# H-bro_gear.net
KiCad netlist of a schematic drawn in EAGLE
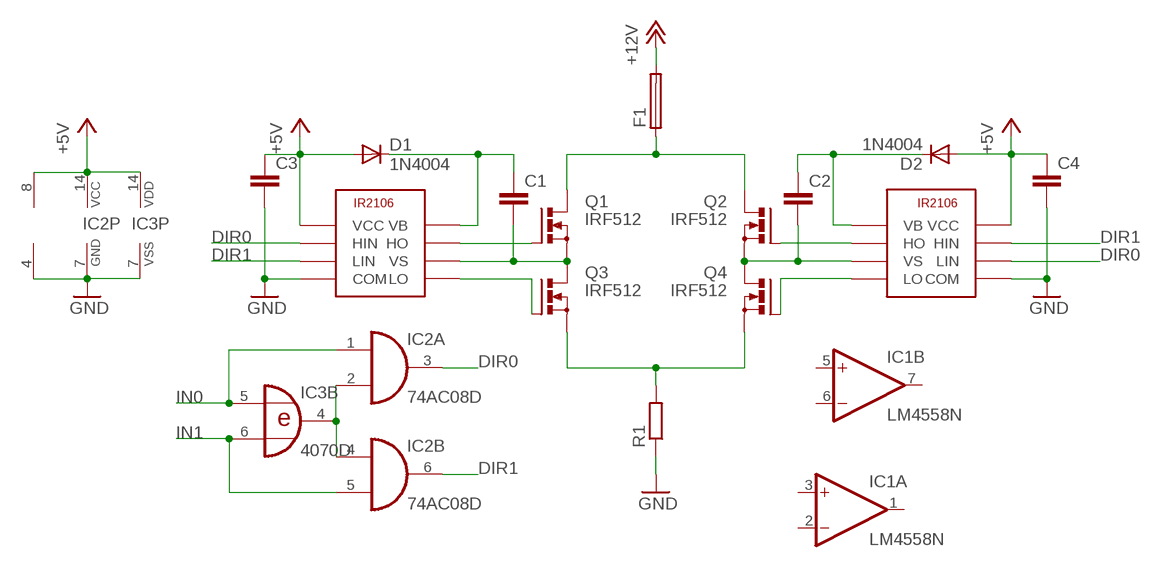
[diagram p0: schematic, sheet 1]

(export (version "E")
  (design (tool "Eeschema 10.0.6"))
  (components
    (comp (ref "C1")
      (value "C-EU025-025X050")
      (footprint "eagle-import:C025-025X050")
      (libsource (lib "eagle-import") (part "C-EU025-025X050"))
    )
    (comp (ref "C2")
      (value "C-EU025-025X050")
      (footprint "eagle-import:C025-025X050")
      (libsource (lib "eagle-import") (part "C-EU025-025X050"))
    )
    (comp (ref "C3")
      (value "C-EU025-025X050")
      (footprint "eagle-import:C025-025X050")
      (libsource (lib "eagle-import") (part "C-EU025-025X050"))
    )
    (comp (ref "C4")
      (value "C-EU025-025X050")
      (footprint "eagle-import:C025-025X050")
      (libsource (lib "eagle-import") (part "C-EU025-025X050"))
    )
    (comp (ref "D1")
      (value "1N4004")
      (footprint "eagle-import:DO41-10")
      (libsource (lib "eagle-import") (part "1N4004"))
    )
    (comp (ref "D2")
      (value "1N4004")
      (footprint "eagle-import:DO41-10")
      (libsource (lib "eagle-import") (part "1N4004"))
    )
    (comp (ref "F1")
      (value "PICOFUSE")
      (footprint "eagle-import:PICOFUSE")
      (libsource (lib "eagle-import") (part "PICOFUSE"))
    )
    (comp (ref "IC1")
      (value "LM4558N")
      (footprint "eagle-import:DIL08")
      (libsource (lib "eagle-import") (part "4558NLM"))
    )
    (comp (ref "IC2")
      (value "74AC08D")
      (footprint "eagle-import:SO14")
      (libsource (lib "eagle-import") (part "7408DAC"))
    )
    (comp (ref "IC3")
      (value "4070D")
      (footprint "eagle-import:SO14")
      (libsource (lib "eagle-import") (part "4070D"))
    )
    (comp (ref "Q1")
      (value "IRF512")
      (footprint "eagle-import:TO220BV")
      (libsource (lib "eagle-import") (part "IRF512"))
    )
    (comp (ref "Q2")
      (value "IRF512")
      (footprint "eagle-import:TO220BV")
      (libsource (lib "eagle-import") (part "IRF512"))
    )
    (comp (ref "Q3")
      (value "IRF512")
      (footprint "eagle-import:TO220BV")
      (libsource (lib "eagle-import") (part "IRF512"))
    )
    (comp (ref "Q4")
      (value "IRF512")
      (footprint "eagle-import:TO220BV")
      (libsource (lib "eagle-import") (part "IRF512"))
    )
    (comp (ref "R1")
      (value "R-EU_0309/12")
      (footprint "eagle-import:0309_12")
      (libsource (lib "eagle-import") (part "R-EU_0309/12"))
    )
    (comp (ref "U$1")
      (value "IR2106")
      (footprint "eagle-import:IR2106")
      (libsource (lib "eagle-import") (part "IR2106"))
    )
    (comp (ref "U$2")
      (value "IR2106")
      (footprint "eagle-import:IR2106")
      (libsource (lib "eagle-import") (part "IR2106"))
    )
  )
  (nets
    (net (code "1") (name "+5V") (class "Default")
      (node (ref "C3") (pin "1") (pinfunction "1_1") (pintype "passive"))
      (node (ref "C4") (pin "1") (pinfunction "1_1") (pintype "passive"))
      (node (ref "D1") (pin "A") (pinfunction "A_A") (pintype "passive"))
      (node (ref "D2") (pin "A") (pinfunction "A_A") (pintype "passive"))
      (node (ref "IC1") (pin "8") (pinfunction "V+_8") (pintype "power_in"))
      (node (ref "IC2") (pin "14") (pinfunction "VCC_14") (pintype "power_in"))
      (node (ref "IC3") (pin "14") (pinfunction "VDD_14") (pintype "power_in"))
      (node (ref "U$1") (pin "VCC") (pinfunction "VCC_VCC") (pintype "bidirectional"))
      (node (ref "U$2") (pin "VCC") (pinfunction "VCC_VCC") (pintype "bidirectional"))
    )
    (net (code "2") (name "+12V") (class "Default")
      (node (ref "F1") (pin "2") (pinfunction "2_2") (pintype "passive"))
    )
    (net (code "3") (name "/DIR0") (class "Default")
      (node (ref "IC2") (pin "3") (pinfunction "O_3") (pintype "output"))
      (node (ref "U$1") (pin "HIN") (pinfunction "HIN_HIN") (pintype "bidirectional"))
      (node (ref "U$2") (pin "LIN") (pinfunction "LIN_LIN") (pintype "bidirectional"))
    )
    (net (code "4") (name "/DIR1") (class "Default")
      (node (ref "IC2") (pin "6") (pinfunction "O_6") (pintype "output"))
      (node (ref "U$1") (pin "LIN") (pinfunction "LIN_LIN") (pintype "bidirectional"))
      (node (ref "U$2") (pin "HIN") (pinfunction "HIN_HIN") (pintype "bidirectional"))
    )
    (net (code "5") (name "/IN0") (class "Default")
      (node (ref "IC2") (pin "1") (pinfunction "I0_1") (pintype "input"))
      (node (ref "IC3") (pin "5") (pinfunction "I0_5") (pintype "input"))
    )
    (net (code "6") (name "/IN1") (class "Default")
      (node (ref "IC2") (pin "5") (pinfunction "I1_5") (pintype "input"))
      (node (ref "IC3") (pin "6") (pinfunction "I1_6") (pintype "input"))
    )
    (net (code "7") (name "GND") (class "Default")
      (node (ref "C3") (pin "2") (pinfunction "2_2") (pintype "passive"))
      (node (ref "C4") (pin "2") (pinfunction "2_2") (pintype "passive"))
      (node (ref "IC1") (pin "4") (pinfunction "V-_4") (pintype "power_in"))
      (node (ref "IC2") (pin "7") (pinfunction "GND_7") (pintype "power_in"))
      (node (ref "IC3") (pin "7") (pinfunction "VSS_7") (pintype "power_in"))
      (node (ref "R1") (pin "1") (pinfunction "1_1") (pintype "passive"))
      (node (ref "U$1") (pin "COM") (pinfunction "COM_COM") (pintype "bidirectional"))
      (node (ref "U$2") (pin "COM") (pinfunction "COM_COM") (pintype "bidirectional"))
    )
    (net (code "8") (name "Net-(C1-Pad1)") (class "Default")
      (node (ref "C1") (pin "1") (pinfunction "1_1") (pintype "passive"))
      (node (ref "D1") (pin "C") (pinfunction "C_C") (pintype "passive"))
      (node (ref "U$1") (pin "VB") (pinfunction "VB_VB") (pintype "bidirectional"))
    )
    (net (code "9") (name "Net-(C1-Pad2)") (class "Default")
      (node (ref "C1") (pin "2") (pinfunction "2_2") (pintype "passive"))
      (node (ref "Q1") (pin "S") (pinfunction "S_S") (pintype "passive"))
      (node (ref "Q3") (pin "D") (pinfunction "D_D") (pintype "passive"))
      (node (ref "U$1") (pin "VS") (pinfunction "VS_VS") (pintype "bidirectional"))
    )
    (net (code "10") (name "Net-(C2-Pad1)") (class "Default")
      (node (ref "C2") (pin "1") (pinfunction "1_1") (pintype "passive"))
      (node (ref "D2") (pin "C") (pinfunction "C_C") (pintype "passive"))
      (node (ref "U$2") (pin "VB") (pinfunction "VB_VB") (pintype "bidirectional"))
    )
    (net (code "11") (name "Net-(C2-Pad2)") (class "Default")
      (node (ref "C2") (pin "2") (pinfunction "2_2") (pintype "passive"))
      (node (ref "Q2") (pin "S") (pinfunction "S_S") (pintype "passive"))
      (node (ref "Q4") (pin "D") (pinfunction "D_D") (pintype "passive"))
      (node (ref "U$2") (pin "VS") (pinfunction "VS_VS") (pintype "bidirectional"))
    )
    (net (code "12") (name "Net-(F1-Pad1)") (class "Default")
      (node (ref "F1") (pin "1") (pinfunction "1_1") (pintype "passive"))
      (node (ref "Q1") (pin "D") (pinfunction "D_D") (pintype "passive"))
      (node (ref "Q2") (pin "D") (pinfunction "D_D") (pintype "passive"))
    )
    (net (code "13") (name "Net-(IC2A-I1)") (class "Default")
      (node (ref "IC2") (pin "2") (pinfunction "I1_2") (pintype "input"))
      (node (ref "IC2") (pin "4") (pinfunction "I0_4") (pintype "input"))
      (node (ref "IC3") (pin "4") (pinfunction "O_4") (pintype "output"))
    )
    (net (code "14") (name "Net-(Q1-PadG)") (class "Default")
      (node (ref "Q1") (pin "G") (pinfunction "G_G") (pintype "passive"))
      (node (ref "U$1") (pin "HO") (pinfunction "HO_HO") (pintype "bidirectional"))
    )
    (net (code "15") (name "Net-(Q2-PadG)") (class "Default")
      (node (ref "Q2") (pin "G") (pinfunction "G_G") (pintype "passive"))
      (node (ref "U$2") (pin "HO") (pinfunction "HO_HO") (pintype "bidirectional"))
    )
    (net (code "16") (name "Net-(Q3-PadG)") (class "Default")
      (node (ref "Q3") (pin "G") (pinfunction "G_G") (pintype "passive"))
      (node (ref "U$1") (pin "LO") (pinfunction "LO_LO") (pintype "bidirectional"))
    )
    (net (code "17") (name "Net-(Q3-PadS)") (class "Default")
      (node (ref "Q3") (pin "S") (pinfunction "S_S") (pintype "passive"))
      (node (ref "Q4") (pin "S") (pinfunction "S_S") (pintype "passive"))
      (node (ref "R1") (pin "2") (pinfunction "2_2") (pintype "passive"))
    )
    (net (code "18") (name "Net-(Q4-PadG)") (class "Default")
      (node (ref "Q4") (pin "G") (pinfunction "G_G") (pintype "passive"))
      (node (ref "U$2") (pin "LO") (pinfunction "LO_LO") (pintype "bidirectional"))
    )
    (net (code "19") (name "unconnected-(IC1A-+IN-Pad3)") (class "Default")
      (node (ref "IC1") (pin "3") (pinfunction "+IN_3") (pintype "input"))
    )
    (net (code "20") (name "unconnected-(IC1A--IN-Pad2)") (class "Default")
      (node (ref "IC1") (pin "2") (pinfunction "-IN_2") (pintype "input"))
    )
    (net (code "21") (name "unconnected-(IC1A-OUT-Pad1)") (class "Default")
      (node (ref "IC1") (pin "1") (pinfunction "OUT_1") (pintype "output"))
    )
    (net (code "22") (name "unconnected-(IC1B-+IN-Pad5)") (class "Default")
      (node (ref "IC1") (pin "5") (pinfunction "+IN_5") (pintype "input"))
    )
    (net (code "23") (name "unconnected-(IC1B--IN-Pad6)") (class "Default")
      (node (ref "IC1") (pin "6") (pinfunction "-IN_6") (pintype "input"))
    )
    (net (code "24") (name "unconnected-(IC1B-OUT-Pad7)") (class "Default")
      (node (ref "IC1") (pin "7") (pinfunction "OUT_7") (pintype "output"))
    )
  )
)
